# Sensors.net
KiCad netlist of a schematic drawn in Altium Designer
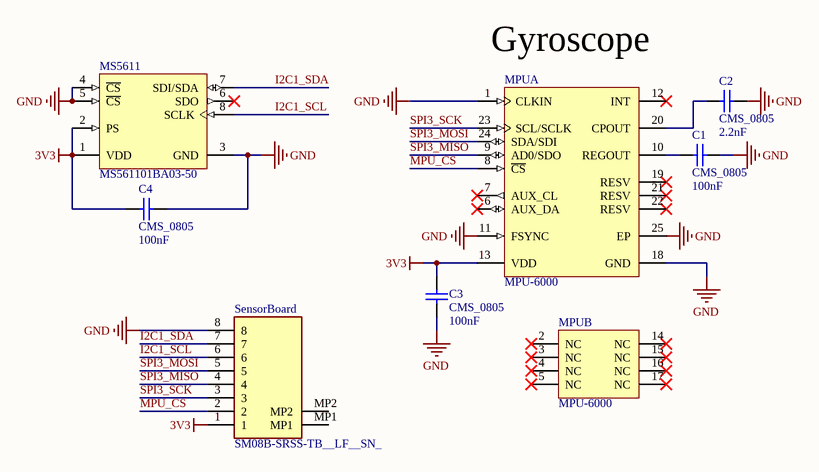
[diagram p0: Sensors.SchDoc]

(export (version "E")
  (design (tool "Eeschema 10.0.6"))
  (components
    (comp (ref "C1")
      (value "100nF")
      (footprint "CONDENSATEUR_CMS_0805")
      (description "CONDENSATEUR CMS CERAMIQUE 0805")
      (fields (field (name "TYPE") "CMS_0805") (field (name "Comment") "CMS_0805"))
      (libsource (lib "composants passifs") (part "CONDENSATEUR_CMS_CER_0805"))
    )
    (comp (ref "C2")
      (value "2.2nF")
      (footprint "CONDENSATEUR_CMS_0805")
      (description "CONDENSATEUR CMS CERAMIQUE 0805")
      (fields (field (name "TYPE") "CMS_0805") (field (name "Comment") "CMS_0805"))
      (libsource (lib "composants passifs") (part "CONDENSATEUR_CMS_CER_0805"))
    )
    (comp (ref "C3")
      (value "100nF")
      (footprint "CONDENSATEUR_CMS_0805")
      (description "CONDENSATEUR CMS CERAMIQUE 0805")
      (fields (field (name "TYPE") "CMS_0805") (field (name "Comment") "CMS_0805"))
      (libsource (lib "composants passifs") (part "CONDENSATEUR_CMS_CER_0805"))
    )
    (comp (ref "C4")
      (value "100nF")
      (footprint "CONDENSATEUR_CMS_0805")
      (description "CONDENSATEUR CMS CERAMIQUE 0805")
      (fields (field (name "TYPE") "CMS_0805") (field (name "Comment") "CMS_0805"))
      (libsource (lib "composants passifs") (part "CONDENSATEUR_CMS_CER_0805"))
    )
    (comp (ref "MPU")
      (value "MPU-6000")
      (footprint "INSE-QFN-24_V")
      (fields (field (name "MANUFACTURER") "InvenSense"))
      (libsource (lib "Altium Content Vault") (part "INSE-MPU-6000"))
    )
    (comp (ref "MS5611")
      (value "MS561101BA03-50")
      (footprint "MSI-MS561101BA03-50-8_V")
      (fields (field (name "MANUFACTURER") "Measurement Specialties"))
      (libsource (lib "Altium Content Vault") (part "MSI-MS561101BA03-50-8"))
    )
    (comp (ref "SensorBoard")
      (value "SM08B-SRSS-TB__LF__SN_")
      (footprint "SamacSys:SM08BSRSSTBLFSN")
      (description "Connector")
      (fields (field (name "MANUFACTURER_PART_NUMBER") "SM08B-SRSS-TB (LF)(SN)"))
      (libsource (lib "*") (part "SM08B-SRSS-TB__LF__SN_"))
    )
  )
  (nets
    (net (code "1") (name "/I2C1_SCL") (class "Default")
      (node (ref "MS5611") (pin "8") (pinfunction "SCLK_8") (pintype "input"))
      (node (ref "SensorBoard") (pin "6") (pinfunction "6_6") (pintype "passive"))
    )
    (net (code "2") (name "/I2C1_SDA") (class "Default")
      (node (ref "MS5611") (pin "7") (pinfunction "SDI/SDA_7") (pintype "bidirectional"))
      (node (ref "SensorBoard") (pin "7") (pinfunction "7_7") (pintype "passive"))
    )
    (net (code "3") (name "/MPU_CS") (class "Default")
      (node (ref "MPU") (pin "8") (pinfunction "~{CS}_8") (pintype "input"))
      (node (ref "SensorBoard") (pin "2") (pinfunction "2_2") (pintype "passive"))
    )
    (net (code "4") (name "/SPI3_MISO") (class "Default")
      (node (ref "MPU") (pin "9") (pinfunction "AD0/SDO_9") (pintype "bidirectional"))
      (node (ref "SensorBoard") (pin "4") (pinfunction "4_4") (pintype "passive"))
    )
    (net (code "5") (name "/SPI3_MOSI") (class "Default")
      (node (ref "MPU") (pin "24") (pinfunction "SDA/SDI_24") (pintype "bidirectional"))
      (node (ref "SensorBoard") (pin "5") (pinfunction "5_5") (pintype "passive"))
    )
    (net (code "6") (name "/SPI3_SCK") (class "Default")
      (node (ref "MPU") (pin "23") (pinfunction "SCL/SCLK_23") (pintype "input"))
      (node (ref "SensorBoard") (pin "3") (pinfunction "3_3") (pintype "passive"))
    )
    (net (code "7") (name "3V3") (class "Default")
      (node (ref "C3") (pin "2") (pinfunction "2_2") (pintype "passive"))
      (node (ref "C4") (pin "2") (pinfunction "2_2") (pintype "passive"))
      (node (ref "MPU") (pin "13") (pinfunction "VDD_13") (pintype "power_in"))
      (node (ref "MS5611") (pin "1") (pinfunction "VDD_1") (pintype "power_in"))
      (node (ref "MS5611") (pin "2") (pinfunction "PS_2") (pintype "input"))
      (node (ref "SensorBoard") (pin "1") (pinfunction "1_1") (pintype "passive"))
    )
    (net (code "8") (name "GND") (class "Default")
      (node (ref "C1") (pin "2") (pinfunction "2_2") (pintype "passive"))
      (node (ref "C2") (pin "2") (pinfunction "2_2") (pintype "passive"))
      (node (ref "C3") (pin "1") (pinfunction "1_1") (pintype "passive"))
      (node (ref "C4") (pin "1") (pinfunction "1_1") (pintype "passive"))
      (node (ref "MPU") (pin "1") (pinfunction "CLKIN_1") (pintype "input"))
      (node (ref "MPU") (pin "11") (pinfunction "FSYNC_11") (pintype "input"))
      (node (ref "MPU") (pin "18") (pinfunction "GND_18") (pintype "power_in"))
      (node (ref "MPU") (pin "25") (pinfunction "EP_25") (pintype "passive"))
      (node (ref "MS5611") (pin "3") (pinfunction "GND_3") (pintype "power_in"))
      (node (ref "MS5611") (pin "4") (pinfunction "~{CS}_4") (pintype "input"))
      (node (ref "MS5611") (pin "5") (pinfunction "~{CS}_5") (pintype "input"))
      (node (ref "SensorBoard") (pin "8") (pinfunction "8_8") (pintype "passive"))
    )
    (net (code "9") (name "Net-(MPUA-CPOUT)") (class "Default")
      (node (ref "C2") (pin "1") (pinfunction "1_1") (pintype "passive"))
      (node (ref "MPU") (pin "20") (pinfunction "CPOUT_20") (pintype "passive"))
    )
    (net (code "10") (name "Net-(MPUA-REGOUT)") (class "Default")
      (node (ref "C1") (pin "1") (pinfunction "1_1") (pintype "passive"))
      (node (ref "MPU") (pin "10") (pinfunction "REGOUT_10") (pintype "passive"))
    )
    (net (code "11") (name "unconnected-(MPUA-AUX_CL-Pad7)") (class "Default")
      (node (ref "MPU") (pin "7") (pinfunction "AUX_CL_7") (pintype "output+no_connect"))
    )
    (net (code "12") (name "unconnected-(MPUA-AUX_DA-Pad6)") (class "Default")
      (node (ref "MPU") (pin "6") (pinfunction "AUX_DA_6") (pintype "bidirectional+no_connect"))
    )
    (net (code "13") (name "unconnected-(MPUA-INT-Pad12)") (class "Default")
      (node (ref "MPU") (pin "12") (pinfunction "INT_12") (pintype "open_collector+no_connect"))
    )
    (net (code "14") (name "unconnected-(MPUA-RESV-Pad19)") (class "Default")
      (node (ref "MPU") (pin "19") (pinfunction "RESV_19") (pintype "passive+no_connect"))
    )
    (net (code "15") (name "unconnected-(MPUA-RESV-Pad21)") (class "Default")
      (node (ref "MPU") (pin "21") (pinfunction "RESV_21") (pintype "passive+no_connect"))
    )
    (net (code "16") (name "unconnected-(MPUA-RESV-Pad22)") (class "Default")
      (node (ref "MPU") (pin "22") (pinfunction "RESV_22") (pintype "passive+no_connect"))
    )
    (net (code "17") (name "unconnected-(MPUB-NC-Pad2)") (class "Default")
      (node (ref "MPU") (pin "2") (pinfunction "NC_2") (pintype "passive+no_connect"))
    )
    (net (code "18") (name "unconnected-(MPUB-NC-Pad3)") (class "Default")
      (node (ref "MPU") (pin "3") (pinfunction "NC_3") (pintype "passive+no_connect"))
    )
    (net (code "19") (name "unconnected-(MPUB-NC-Pad4)") (class "Default")
      (node (ref "MPU") (pin "4") (pinfunction "NC_4") (pintype "passive+no_connect"))
    )
    (net (code "20") (name "unconnected-(MPUB-NC-Pad5)") (class "Default")
      (node (ref "MPU") (pin "5") (pinfunction "NC_5") (pintype "passive+no_connect"))
    )
    (net (code "21") (name "unconnected-(MPUB-NC-Pad14)") (class "Default")
      (node (ref "MPU") (pin "14") (pinfunction "NC_14") (pintype "passive+no_connect"))
    )
    (net (code "22") (name "unconnected-(MPUB-NC-Pad15)") (class "Default")
      (node (ref "MPU") (pin "15") (pinfunction "NC_15") (pintype "passive+no_connect"))
    )
    (net (code "23") (name "unconnected-(MPUB-NC-Pad16)") (class "Default")
      (node (ref "MPU") (pin "16") (pinfunction "NC_16") (pintype "passive+no_connect"))
    )
    (net (code "24") (name "unconnected-(MPUB-NC-Pad17)") (class "Default")
      (node (ref "MPU") (pin "17") (pinfunction "NC_17") (pintype "passive+no_connect"))
    )
    (net (code "25") (name "unconnected-(MS5611-SDO-Pad6)") (class "Default")
      (node (ref "MS5611") (pin "6") (pinfunction "SDO_6") (pintype "output+no_connect"))
    )
    (net (code "26") (name "unconnected-(SensorBoard-PadMP1)") (class "Default")
      (node (ref "SensorBoard") (pin "MP1") (pinfunction "MP1_MP1") (pintype "passive"))
    )
    (net (code "27") (name "unconnected-(SensorBoard-PadMP2)") (class "Default")
      (node (ref "SensorBoard") (pin "MP2") (pinfunction "MP2_MP2") (pintype "passive"))
    )
  )
)
